# sw-4416-project-v1.net
KiCad netlist of a schematic drawn in EAGLE
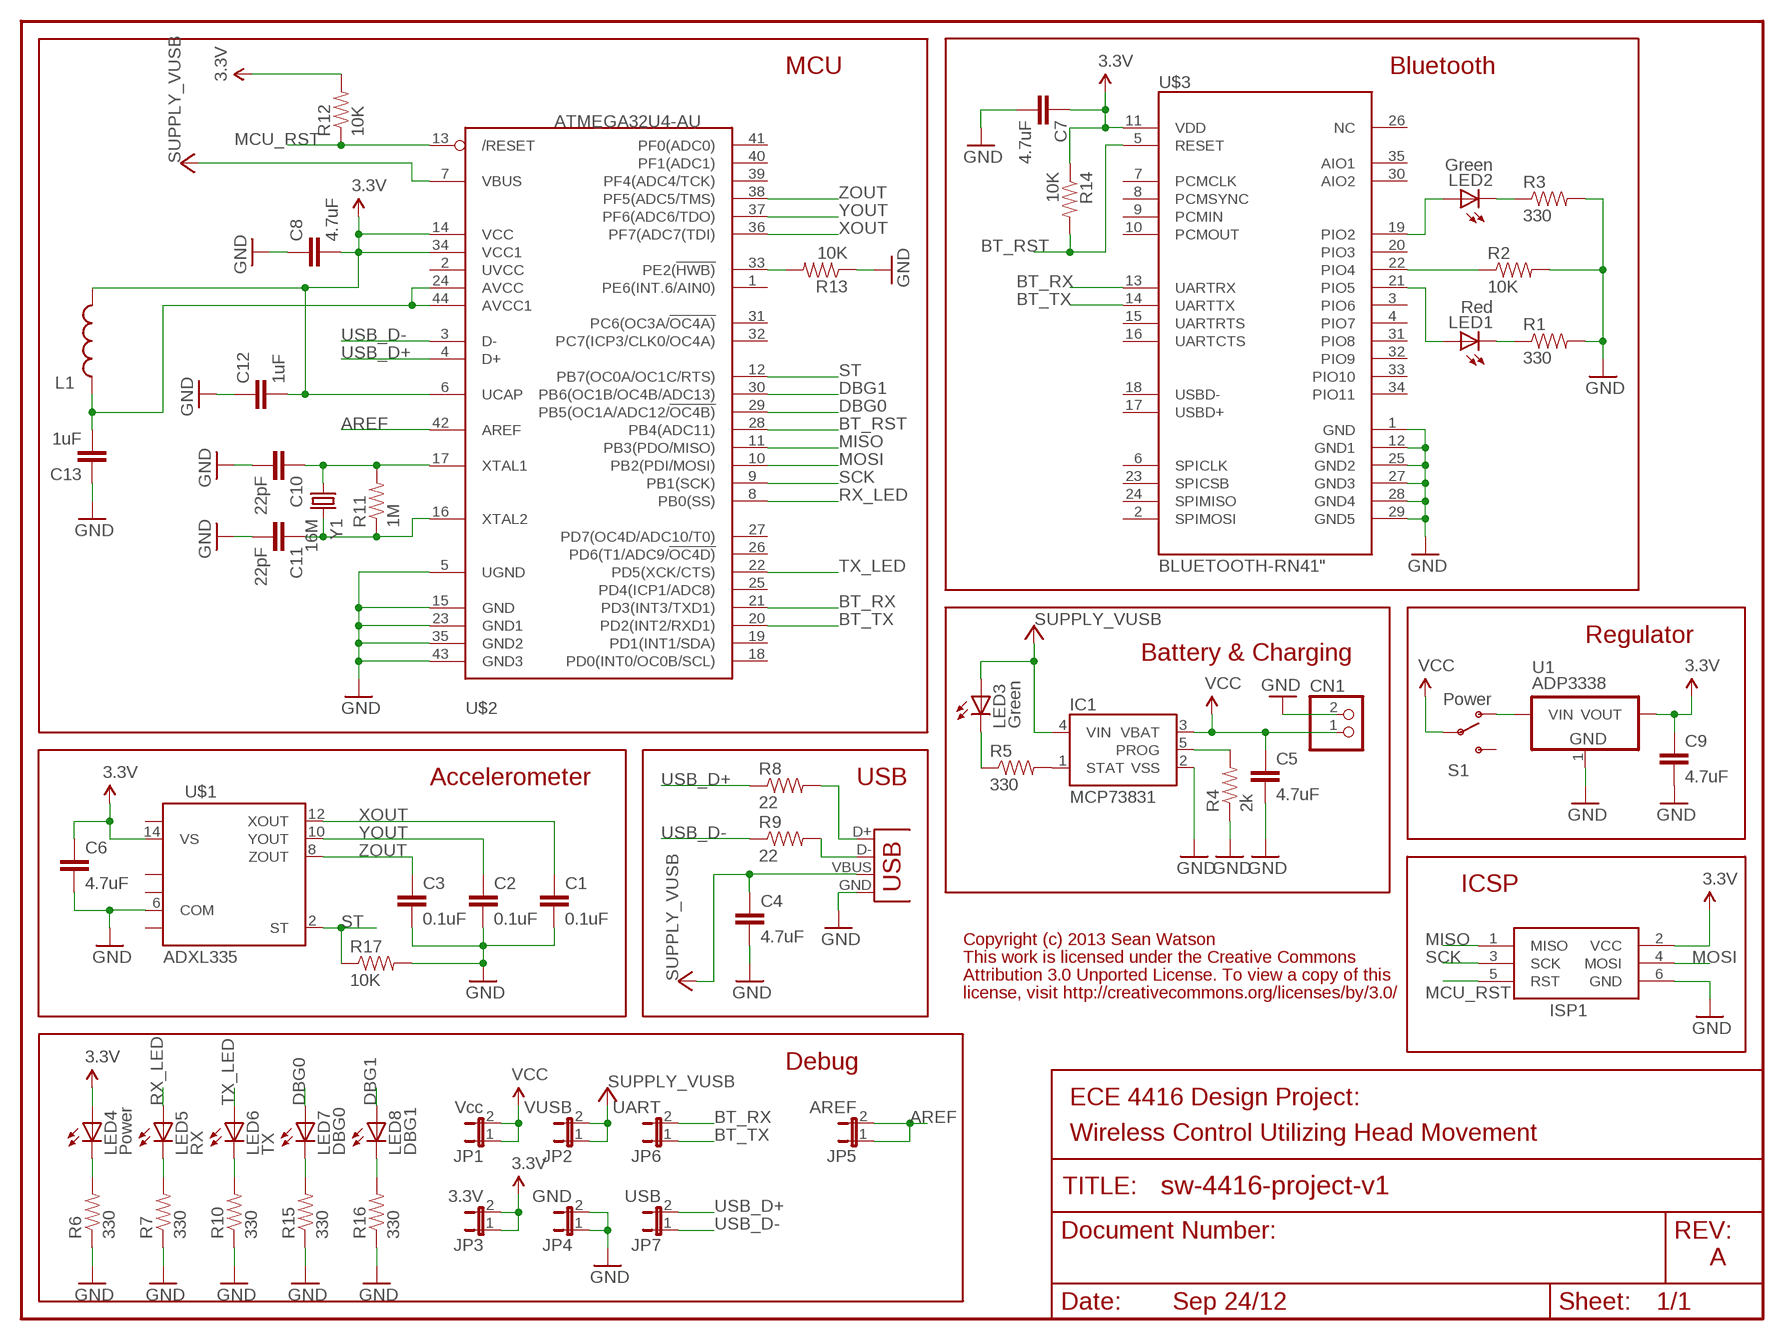
[diagram p0: schematic, sheet 1]

(export (version "E")
  (design (tool "Eeschema 10.0.6"))
  (components
    (comp (ref "C1")
      (value "0.1uF")
      (footprint "eagle-import:0603-CAP")
      (libsource (lib "eagle-import") (part "CAP0603-CAP"))
    )
    (comp (ref "C2")
      (value "0.1uF")
      (footprint "eagle-import:0603-CAP")
      (libsource (lib "eagle-import") (part "CAP0603-CAP"))
    )
    (comp (ref "C3")
      (value "0.1uF")
      (footprint "eagle-import:0603-CAP")
      (libsource (lib "eagle-import") (part "CAP0603-CAP"))
    )
    (comp (ref "C4")
      (value "4.7uF")
      (footprint "eagle-import:0603-CAP")
      (libsource (lib "eagle-import") (part "CAP0603-CAP"))
    )
    (comp (ref "C5")
      (value "4.7uF")
      (footprint "eagle-import:0603-CAP")
      (libsource (lib "eagle-import") (part "CAP0603-CAP"))
    )
    (comp (ref "C6")
      (value "4.7uF")
      (footprint "eagle-import:0603-CAP")
      (libsource (lib "eagle-import") (part "CAP0603-CAP"))
    )
    (comp (ref "C7")
      (value "4.7uF")
      (footprint "eagle-import:0603-CAP")
      (libsource (lib "eagle-import") (part "CAP0603-CAP"))
    )
    (comp (ref "C8")
      (value "4.7uF")
      (footprint "eagle-import:0603-CAP")
      (libsource (lib "eagle-import") (part "CAP0603-CAP"))
    )
    (comp (ref "C9")
      (value "4.7uF")
      (footprint "eagle-import:0603-CAP")
      (libsource (lib "eagle-import") (part "CAP0603-CAP"))
    )
    (comp (ref "C10")
      (value "22pF")
      (footprint "eagle-import:0603-CAP")
      (libsource (lib "eagle-import") (part "CAP0603-CAP"))
    )
    (comp (ref "C11")
      (value "22pF")
      (footprint "eagle-import:0603-CAP")
      (libsource (lib "eagle-import") (part "CAP0603-CAP"))
    )
    (comp (ref "C12")
      (value "1uF")
      (footprint "eagle-import:0603-CAP")
      (libsource (lib "eagle-import") (part "CAP0603-CAP"))
    )
    (comp (ref "C13")
      (value "1uF")
      (footprint "eagle-import:0603-CAP")
      (libsource (lib "eagle-import") (part "CAP0603-CAP"))
    )
    (comp (ref "CN1")
      (value "JST_2PIN-SMT-RA")
      (footprint "eagle-import:JST-PH-2-SMT-RA")
      (libsource (lib "eagle-import") (part "JST_2PIN-SMT-RA"))
    )
    (comp (ref "IC1")
      (value "MCP73831")
      (footprint "eagle-import:SOT23-5")
      (libsource (lib "eagle-import") (part "MCP73831"))
    )
    (comp (ref "ISP1")
      (value "AVRISP-6")
      (footprint "eagle-import:AVRISP")
      (libsource (lib "eagle-import") (part "AVRISP-6"))
    )
    (comp (ref "JP1")
      (value "Vcc")
      (footprint "eagle-import:1X02")
      (libsource (lib "eagle-import") (part "JUMPER-2PTH"))
    )
    (comp (ref "JP2")
      (value "VUSB")
      (footprint "eagle-import:1X02")
      (libsource (lib "eagle-import") (part "JUMPER-2PTH"))
    )
    (comp (ref "JP3")
      (value "3.3V")
      (footprint "eagle-import:1X02")
      (libsource (lib "eagle-import") (part "JUMPER-2PTH"))
    )
    (comp (ref "JP4")
      (value "GND")
      (footprint "eagle-import:1X02")
      (libsource (lib "eagle-import") (part "JUMPER-2PTH"))
    )
    (comp (ref "JP5")
      (value "AREF")
      (footprint "eagle-import:1X02")
      (libsource (lib "eagle-import") (part "JUMPER-2PTH"))
    )
    (comp (ref "JP6")
      (value "UART")
      (footprint "eagle-import:1X02")
      (libsource (lib "eagle-import") (part "JUMPER-2PTH"))
    )
    (comp (ref "JP7")
      (value "USB")
      (footprint "eagle-import:1X02")
      (libsource (lib "eagle-import") (part "JUMPER-2PTH"))
    )
    (comp (ref "L1")
      (value "INDUCTOR0805")
      (footprint "eagle-import:0805")
      (libsource (lib "eagle-import") (part "INDUCTOR0805"))
    )
    (comp (ref "LED1")
      (value "Red")
      (footprint "eagle-import:LED-0603")
      (libsource (lib "eagle-import") (part "LED0603"))
    )
    (comp (ref "LED2")
      (value "Green")
      (footprint "eagle-import:LED-0603")
      (libsource (lib "eagle-import") (part "LED0603"))
    )
    (comp (ref "LED3")
      (value "Green")
      (footprint "eagle-import:LED-0603")
      (libsource (lib "eagle-import") (part "LED0603"))
    )
    (comp (ref "LED4")
      (value "Power")
      (footprint "eagle-import:LED-0603")
      (libsource (lib "eagle-import") (part "LED0603"))
    )
    (comp (ref "LED5")
      (value "RX")
      (footprint "eagle-import:LED-0603")
      (libsource (lib "eagle-import") (part "LED0603"))
    )
    (comp (ref "LED6")
      (value "TX")
      (footprint "eagle-import:LED-0603")
      (libsource (lib "eagle-import") (part "LED0603"))
    )
    (comp (ref "LED7")
      (value "DBG0")
      (footprint "eagle-import:LED-0603")
      (libsource (lib "eagle-import") (part "LED0603"))
    )
    (comp (ref "LED8")
      (value "DBG1")
      (footprint "eagle-import:LED-0603")
      (libsource (lib "eagle-import") (part "LED0603"))
    )
    (comp (ref "R1")
      (value "330")
      (footprint "eagle-import:0603-RES")
      (libsource (lib "eagle-import") (part "RESISTOR0603-RES"))
    )
    (comp (ref "R2")
      (value "10K")
      (footprint "eagle-import:0603-RES")
      (libsource (lib "eagle-import") (part "RESISTOR0603-RES"))
    )
    (comp (ref "R3")
      (value "330")
      (footprint "eagle-import:0603-RES")
      (libsource (lib "eagle-import") (part "RESISTOR0603-RES"))
    )
    (comp (ref "R4")
      (value "2k")
      (footprint "eagle-import:0603-RES")
      (libsource (lib "eagle-import") (part "RESISTOR0603-RES"))
    )
    (comp (ref "R5")
      (value "330")
      (footprint "eagle-import:0603-RES")
      (libsource (lib "eagle-import") (part "RESISTOR0603-RES"))
    )
    (comp (ref "R6")
      (value "330")
      (footprint "eagle-import:0603-RES")
      (libsource (lib "eagle-import") (part "RESISTOR0603-RES"))
    )
    (comp (ref "R7")
      (value "330")
      (footprint "eagle-import:0603-RES")
      (libsource (lib "eagle-import") (part "RESISTOR0603-RES"))
    )
    (comp (ref "R8")
      (value "22")
      (footprint "eagle-import:0603-RES")
      (libsource (lib "eagle-import") (part "RESISTOR0603-RES"))
    )
    (comp (ref "R9")
      (value "22")
      (footprint "eagle-import:0603-RES")
      (libsource (lib "eagle-import") (part "RESISTOR0603-RES"))
    )
    (comp (ref "R10")
      (value "330")
      (footprint "eagle-import:0603-RES")
      (libsource (lib "eagle-import") (part "RESISTOR0603-RES"))
    )
    (comp (ref "R11")
      (value "1M")
      (footprint "eagle-import:0603-RES")
      (libsource (lib "eagle-import") (part "RESISTOR0603-RES"))
    )
    (comp (ref "R12")
      (value "10K")
      (footprint "eagle-import:0603-RES")
      (libsource (lib "eagle-import") (part "RESISTOR0603-RES"))
    )
    (comp (ref "R13")
      (value "10K")
      (footprint "eagle-import:0603-RES")
      (libsource (lib "eagle-import") (part "RESISTOR0603-RES"))
    )
    (comp (ref "R14")
      (value "10K")
      (footprint "eagle-import:0603-RES")
      (libsource (lib "eagle-import") (part "RESISTOR0603-RES"))
    )
    (comp (ref "R15")
      (value "330")
      (footprint "eagle-import:0603-RES")
      (libsource (lib "eagle-import") (part "RESISTOR0603-RES"))
    )
    (comp (ref "R16")
      (value "330")
      (footprint "eagle-import:0603-RES")
      (libsource (lib "eagle-import") (part "RESISTOR0603-RES"))
    )
    (comp (ref "R17")
      (value "10K")
      (footprint "eagle-import:0603-RES")
      (libsource (lib "eagle-import") (part "RESISTOR0603-RES"))
    )
    (comp (ref "S1")
      (value "Power")
      (footprint "eagle-import:SWITCH-SPST-SMD-A")
      (libsource (lib "eagle-import") (part "SWITCH-SPST-SMD-A"))
    )
    (comp (ref "U$1")
      (value "ADXL335")
      (footprint "eagle-import:LFCSP-16")
      (libsource (lib "eagle-import") (part "ADXL335"))
    )
    (comp (ref "U$2")
      (value "ATMEGA32U4-AU")
      (footprint "eagle-import:TQFP44")
      (libsource (lib "eagle-import") (part "ATMEGA32U4-AU"))
    )
    (comp (ref "U$3")
      (value "BLUETOOTH-RN41\"")
      (footprint "eagle-import:RN41")
      (libsource (lib "eagle-import") (part "BLUETOOTH-RN41{dblquote}"))
    )
    (comp (ref "U1")
      (value "ADP3338")
      (footprint "eagle-import:SOT-223")
      (libsource (lib "eagle-import") (part "VREG_3PINS-SOT-223"))
    )
    (comp (ref "X1")
      (value "USB-MICROB")
      (footprint "eagle-import:USB-MICROB")
      (libsource (lib "eagle-import") (part "USB-MICROB"))
    )
    (comp (ref "Y1")
      (value "16M")
      (footprint "eagle-import:HC49US")
      (libsource (lib "eagle-import") (part "CRYSTALHC49US"))
    )
  )
  (nets
    (net (code "1") (name "/AREF") (class "Default")
      (node (ref "JP5") (pin "1") (pinfunction "1_1") (pintype "passive"))
      (node (ref "JP5") (pin "2") (pinfunction "2_2") (pintype "passive"))
      (node (ref "U$2") (pin "42") (pinfunction "AREF_42") (pintype "bidirectional"))
    )
    (net (code "2") (name "/BT_RST") (class "Default")
      (node (ref "R14") (pin "2") (pinfunction "2_2") (pintype "passive"))
      (node (ref "U$2") (pin "28") (pinfunction "PB4(ADC11)_28") (pintype "bidirectional"))
      (node (ref "U$3") (pin "5") (pinfunction "RESET_5") (pintype "bidirectional"))
    )
    (net (code "3") (name "/BT_RX") (class "Default")
      (node (ref "JP6") (pin "2") (pinfunction "2_2") (pintype "passive"))
      (node (ref "U$2") (pin "21") (pinfunction "PD3(INT3/TXD1)_21") (pintype "bidirectional"))
      (node (ref "U$3") (pin "13") (pinfunction "UARTRX_13") (pintype "bidirectional"))
    )
    (net (code "4") (name "/BT_TX") (class "Default")
      (node (ref "JP6") (pin "1") (pinfunction "1_1") (pintype "passive"))
      (node (ref "U$2") (pin "20") (pinfunction "PD2(INT2/RXD1)_20") (pintype "bidirectional"))
      (node (ref "U$3") (pin "14") (pinfunction "UARTTX_14") (pintype "bidirectional"))
    )
    (net (code "5") (name "/DBG0") (class "Default")
      (node (ref "LED7") (pin "A") (pinfunction "A_A") (pintype "passive"))
      (node (ref "U$2") (pin "29") (pinfunction "PB5(OC1A/ADC12/~{OC4B})_29") (pintype "bidirectional"))
    )
    (net (code "6") (name "/DBG1") (class "Default")
      (node (ref "LED8") (pin "A") (pinfunction "A_A") (pintype "passive"))
      (node (ref "U$2") (pin "30") (pinfunction "PB6(OC1B/OC4B/ADC13)_30") (pintype "bidirectional"))
    )
    (net (code "7") (name "/MCU_RST") (class "Default")
      (node (ref "ISP1") (pin "5") (pinfunction "RST_5") (pintype "output"))
      (node (ref "R12") (pin "1") (pinfunction "1_1") (pintype "passive"))
      (node (ref "U$2") (pin "13") (pinfunction "/RESET_13") (pintype "bidirectional"))
    )
    (net (code "8") (name "/MISO") (class "Default")
      (node (ref "ISP1") (pin "1") (pinfunction "MISO_1") (pintype "input"))
      (node (ref "U$2") (pin "11") (pinfunction "PB3(PDO/MISO)_11") (pintype "bidirectional"))
    )
    (net (code "9") (name "/MOSI") (class "Default")
      (node (ref "ISP1") (pin "4") (pinfunction "MOSI_4") (pintype "output"))
      (node (ref "U$2") (pin "10") (pinfunction "PB2(PDI/MOSI)_10") (pintype "bidirectional"))
    )
    (net (code "10") (name "/RX_LED") (class "Default")
      (node (ref "LED5") (pin "A") (pinfunction "A_A") (pintype "passive"))
      (node (ref "U$2") (pin "8") (pinfunction "PB0(SS)_8") (pintype "bidirectional"))
    )
    (net (code "11") (name "/SCK") (class "Default")
      (node (ref "ISP1") (pin "3") (pinfunction "SCK_3") (pintype "output"))
      (node (ref "U$2") (pin "9") (pinfunction "PB1(SCK)_9") (pintype "bidirectional"))
    )
    (net (code "12") (name "/ST") (class "Default")
      (node (ref "R17") (pin "1") (pinfunction "1_1") (pintype "passive"))
      (node (ref "U$1") (pin "2") (pinfunction "ST_2") (pintype "bidirectional"))
      (node (ref "U$2") (pin "12") (pinfunction "PB7(OC0A/OC1C/RTS)_12") (pintype "bidirectional"))
    )
    (net (code "13") (name "/TX_LED") (class "Default")
      (node (ref "LED6") (pin "A") (pinfunction "A_A") (pintype "passive"))
      (node (ref "U$2") (pin "22") (pinfunction "PD5(XCK/CTS)_22") (pintype "bidirectional"))
    )
    (net (code "14") (name "/USB_D+") (class "Default")
      (node (ref "JP7") (pin "2") (pinfunction "2_2") (pintype "passive"))
      (node (ref "R8") (pin "1") (pinfunction "1_1") (pintype "passive"))
      (node (ref "U$2") (pin "4") (pinfunction "D+_4") (pintype "bidirectional"))
    )
    (net (code "15") (name "/USB_D-") (class "Default")
      (node (ref "JP7") (pin "1") (pinfunction "1_1") (pintype "passive"))
      (node (ref "R9") (pin "1") (pinfunction "1_1") (pintype "passive"))
      (node (ref "U$2") (pin "3") (pinfunction "D-_3") (pintype "bidirectional"))
    )
    (net (code "16") (name "/XOUT") (class "Default")
      (node (ref "C1") (pin "1") (pinfunction "1_1") (pintype "passive"))
      (node (ref "U$1") (pin "12") (pinfunction "XOUT_12") (pintype "bidirectional"))
      (node (ref "U$2") (pin "36") (pinfunction "PF7(ADC7(TDI)_36") (pintype "bidirectional"))
    )
    (net (code "17") (name "/YOUT") (class "Default")
      (node (ref "C2") (pin "1") (pinfunction "1_1") (pintype "passive"))
      (node (ref "U$1") (pin "10") (pinfunction "YOUT_10") (pintype "bidirectional"))
      (node (ref "U$2") (pin "37") (pinfunction "PF6(ADC6/TDO)_37") (pintype "bidirectional"))
    )
    (net (code "18") (name "/ZOUT") (class "Default")
      (node (ref "C3") (pin "1") (pinfunction "1_1") (pintype "passive"))
      (node (ref "U$1") (pin "8") (pinfunction "ZOUT_8") (pintype "bidirectional"))
      (node (ref "U$2") (pin "38") (pinfunction "PF5(ADC5/TMS)_38") (pintype "bidirectional"))
    )
    (net (code "19") (name "3.3V") (class "Default")
      (node (ref "C12") (pin "2") (pinfunction "2_2") (pintype "passive"))
      (node (ref "C6") (pin "1") (pinfunction "1_1") (pintype "passive"))
      (node (ref "C7") (pin "1") (pinfunction "1_1") (pintype "passive"))
      (node (ref "C8") (pin "2") (pinfunction "2_2") (pintype "passive"))
      (node (ref "C9") (pin "1") (pinfunction "1_1") (pintype "passive"))
      (node (ref "ISP1") (pin "2") (pinfunction "VCC_2") (pintype "power_in"))
      (node (ref "JP3") (pin "1") (pinfunction "1_1") (pintype "passive"))
      (node (ref "JP3") (pin "2") (pinfunction "2_2") (pintype "passive"))
      (node (ref "L1") (pin "2") (pinfunction "2_2") (pintype "passive"))
      (node (ref "LED4") (pin "A") (pinfunction "A_A") (pintype "passive"))
      (node (ref "R12") (pin "2") (pinfunction "2_2") (pintype "passive"))
      (node (ref "R14") (pin "1") (pinfunction "1_1") (pintype "passive"))
      (node (ref "U$1") (pin "14") (pinfunction "VS_14") (pintype "bidirectional"))
      (node (ref "U$2") (pin "14") (pinfunction "VCC_14") (pintype "bidirectional"))
      (node (ref "U$2") (pin "34") (pinfunction "VCC1_34") (pintype "bidirectional"))
      (node (ref "U$2") (pin "6") (pinfunction "UCAP_6") (pintype "bidirectional"))
      (node (ref "U$3") (pin "11") (pinfunction "VDD_11") (pintype "bidirectional"))
      (node (ref "U1") (pin "2") (pinfunction "VOUT_2") (pintype "bidirectional"))
    )
    (net (code "20") (name "GND") (class "Default")
      (node (ref "C1") (pin "2") (pinfunction "2_2") (pintype "passive"))
      (node (ref "C10") (pin "2") (pinfunction "2_2") (pintype "passive"))
      (node (ref "C11") (pin "2") (pinfunction "2_2") (pintype "passive"))
      (node (ref "C12") (pin "1") (pinfunction "1_1") (pintype "passive"))
      (node (ref "C13") (pin "1") (pinfunction "1_1") (pintype "passive"))
      (node (ref "C2") (pin "2") (pinfunction "2_2") (pintype "passive"))
      (node (ref "C3") (pin "2") (pinfunction "2_2") (pintype "passive"))
      (node (ref "C4") (pin "2") (pinfunction "2_2") (pintype "passive"))
      (node (ref "C5") (pin "2") (pinfunction "2_2") (pintype "passive"))
      (node (ref "C6") (pin "2") (pinfunction "2_2") (pintype "passive"))
      (node (ref "C7") (pin "2") (pinfunction "2_2") (pintype "passive"))
      (node (ref "C8") (pin "1") (pinfunction "1_1") (pintype "passive"))
      (node (ref "C9") (pin "2") (pinfunction "2_2") (pintype "passive"))
      (node (ref "CN1") (pin "2") (pinfunction "1_2") (pintype "passive"))
      (node (ref "IC1") (pin "2") (pinfunction "VSS_2") (pintype "power_in"))
      (node (ref "ISP1") (pin "6") (pinfunction "GND_6") (pintype "power_in"))
      (node (ref "JP4") (pin "1") (pinfunction "1_1") (pintype "passive"))
      (node (ref "JP4") (pin "2") (pinfunction "2_2") (pintype "passive"))
      (node (ref "R1") (pin "2") (pinfunction "2_2") (pintype "passive"))
      (node (ref "R10") (pin "1") (pinfunction "1_1") (pintype "passive"))
      (node (ref "R13") (pin "1") (pinfunction "1_1") (pintype "passive"))
      (node (ref "R15") (pin "1") (pinfunction "1_1") (pintype "passive"))
      (node (ref "R16") (pin "1") (pinfunction "1_1") (pintype "passive"))
      (node (ref "R17") (pin "2") (pinfunction "2_2") (pintype "passive"))
      (node (ref "R2") (pin "2") (pinfunction "2_2") (pintype "passive"))
      (node (ref "R3") (pin "2") (pinfunction "2_2") (pintype "passive"))
      (node (ref "R4") (pin "1") (pinfunction "1_1") (pintype "passive"))
      (node (ref "R6") (pin "1") (pinfunction "1_1") (pintype "passive"))
      (node (ref "R7") (pin "1") (pinfunction "1_1") (pintype "passive"))
      (node (ref "U$1") (pin "6") (pinfunction "COM_6") (pintype "bidirectional"))
      (node (ref "U$2") (pin "15") (pinfunction "GND_15") (pintype "bidirectional"))
      (node (ref "U$2") (pin "23") (pinfunction "GND1_23") (pintype "bidirectional"))
      (node (ref "U$2") (pin "35") (pinfunction "GND2_35") (pintype "bidirectional"))
      (node (ref "U$2") (pin "43") (pinfunction "GND3_43") (pintype "bidirectional"))
      (node (ref "U$2") (pin "5") (pinfunction "UGND_5") (pintype "bidirectional"))
      (node (ref "U$3") (pin "1") (pinfunction "GND_1") (pintype "bidirectional"))
      (node (ref "U$3") (pin "12") (pinfunction "GND1_12") (pintype "bidirectional"))
      (node (ref "U$3") (pin "25") (pinfunction "GND2_25") (pintype "bidirectional"))
      (node (ref "U$3") (pin "27") (pinfunction "GND3_27") (pintype "bidirectional"))
      (node (ref "U$3") (pin "28") (pinfunction "GND4_28") (pintype "bidirectional"))
      (node (ref "U$3") (pin "29") (pinfunction "GND5_29") (pintype "bidirectional"))
      (node (ref "U1") (pin "1") (pinfunction "GND_1") (pintype "bidirectional"))
      (node (ref "X1") (pin "GND") (pinfunction "GND_GND") (pintype "bidirectional"))
    )
    (net (code "21") (name "Net-(IC1-PROG)") (class "Default")
      (node (ref "IC1") (pin "5") (pinfunction "PROG_5") (pintype "input"))
      (node (ref "R4") (pin "2") (pinfunction "2_2") (pintype "passive"))
    )
    (net (code "22") (name "Net-(IC1-STAT)") (class "Default")
      (node (ref "IC1") (pin "1") (pinfunction "STAT_1") (pintype "output"))
      (node (ref "R5") (pin "2") (pinfunction "2_2") (pintype "passive"))
    )
    (net (code "23") (name "Net-(LED1-PadC)") (class "Default")
      (node (ref "LED1") (pin "C") (pinfunction "C_C") (pintype "passive"))
      (node (ref "R1") (pin "1") (pinfunction "1_1") (pintype "passive"))
    )
    (net (code "24") (name "Net-(LED2-PadC)") (class "Default")
      (node (ref "LED2") (pin "C") (pinfunction "C_C") (pintype "passive"))
      (node (ref "R3") (pin "1") (pinfunction "1_1") (pintype "passive"))
    )
    (net (code "25") (name "Net-(LED3-PadC)") (class "Default")
      (node (ref "LED3") (pin "C") (pinfunction "C_C") (pintype "passive"))
      (node (ref "R5") (pin "1") (pinfunction "1_1") (pintype "passive"))
    )
    (net (code "26") (name "Net-(LED4-PadC)") (class "Default")
      (node (ref "LED4") (pin "C") (pinfunction "C_C") (pintype "passive"))
      (node (ref "R6") (pin "2") (pinfunction "2_2") (pintype "passive"))
    )
    (net (code "27") (name "Net-(LED5-PadC)") (class "Default")
      (node (ref "LED5") (pin "C") (pinfunction "C_C") (pintype "passive"))
      (node (ref "R7") (pin "2") (pinfunction "2_2") (pintype "passive"))
    )
    (net (code "28") (name "Net-(LED6-PadC)") (class "Default")
      (node (ref "LED6") (pin "C") (pinfunction "C_C") (pintype "passive"))
      (node (ref "R10") (pin "2") (pinfunction "2_2") (pintype "passive"))
    )
    (net (code "29") (name "Net-(LED7-PadC)") (class "Default")
      (node (ref "LED7") (pin "C") (pinfunction "C_C") (pintype "passive"))
      (node (ref "R15") (pin "2") (pinfunction "2_2") (pintype "passive"))
    )
    (net (code "30") (name "Net-(LED8-PadC)") (class "Default")
      (node (ref "LED8") (pin "C") (pinfunction "C_C") (pintype "passive"))
      (node (ref "R16") (pin "2") (pinfunction "2_2") (pintype "passive"))
    )
    (net (code "31") (name "Net-(R8-Pad2)") (class "Default")
      (node (ref "R8") (pin "2") (pinfunction "2_2") (pintype "passive"))
      (node (ref "X1") (pin "D+") (pinfunction "D+_D+") (pintype "bidirectional"))
    )
    (net (code "32") (name "Net-(R9-Pad2)") (class "Default")
      (node (ref "R9") (pin "2") (pinfunction "2_2") (pintype "passive"))
      (node (ref "X1") (pin "D-") (pinfunction "D-_D-") (pintype "bidirectional"))
    )
    (net (code "33") (name "Net-(S1-O)") (class "Default")
      (node (ref "S1") (pin "1") (pinfunction "O_1") (pintype "passive"))
      (node (ref "U1") (pin "3") (pinfunction "VIN_3") (pintype "bidirectional"))
    )
    (net (code "34") (name "Net-(U$2-AVCC)") (class "Default")
      (node (ref "C13") (pin "2") (pinfunction "2_2") (pintype "passive"))
      (node (ref "L1") (pin "1") (pinfunction "1_1") (pintype "passive"))
      (node (ref "U$2") (pin "24") (pinfunction "AVCC_24") (pintype "bidirectional"))
      (node (ref "U$2") (pin "44") (pinfunction "AVCC1_44") (pintype "bidirectional"))
    )
    (net (code "35") (name "Net-(U$2-PE2(~{HWB}))") (class "Default")
      (node (ref "R13") (pin "2") (pinfunction "2_2") (pintype "passive"))
      (node (ref "U$2") (pin "33") (pinfunction "PE2(~{HWB})_33") (pintype "bidirectional"))
    )
    (net (code "36") (name "Net-(U$2-XTAL1)") (class "Default")
      (node (ref "C10") (pin "1") (pinfunction "1_1") (pintype "passive"))
      (node (ref "R11") (pin "2") (pinfunction "2_2") (pintype "passive"))
      (node (ref "U$2") (pin "17") (pinfunction "XTAL1_17") (pintype "bidirectional"))
      (node (ref "Y1") (pin "1") (pinfunction "1_1") (pintype "passive"))
    )
    (net (code "37") (name "Net-(U$2-XTAL2)") (class "Default")
      (node (ref "C11") (pin "1") (pinfunction "1_1") (pintype "passive"))
      (node (ref "R11") (pin "1") (pinfunction "1_1") (pintype "passive"))
      (node (ref "U$2") (pin "16") (pinfunction "XTAL2_16") (pintype "bidirectional"))
      (node (ref "Y1") (pin "2") (pinfunction "2_2") (pintype "passive"))
    )
    (net (code "38") (name "Net-(U$3-PIO2)") (class "Default")
      (node (ref "LED2") (pin "A") (pinfunction "A_A") (pintype "passive"))
      (node (ref "U$3") (pin "19") (pinfunction "PIO2_19") (pintype "bidirectional"))
    )
    (net (code "39") (name "Net-(U$3-PIO4)") (class "Default")
      (node (ref "R2") (pin "1") (pinfunction "1_1") (pintype "passive"))
      (node (ref "U$3") (pin "22") (pinfunction "PIO4_22") (pintype "bidirectional"))
    )
    (net (code "40") (name "Net-(U$3-PIO5)") (class "Default")
      (node (ref "LED1") (pin "A") (pinfunction "A_A") (pintype "passive"))
      (node (ref "U$3") (pin "21") (pinfunction "PIO5_21") (pintype "bidirectional"))
    )
    (net (code "41") (name "SUPPLY_VUSB") (class "Default")
      (node (ref "C4") (pin "1") (pinfunction "1_1") (pintype "passive"))
      (node (ref "IC1") (pin "4") (pinfunction "VIN_4") (pintype "power_in"))
      (node (ref "JP2") (pin "1") (pinfunction "1_1") (pintype "passive"))
      (node (ref "JP2") (pin "2") (pinfunction "2_2") (pintype "passive"))
      (node (ref "LED3") (pin "A") (pinfunction "A_A") (pintype "passive"))
      (node (ref "U$2") (pin "7") (pinfunction "VBUS_7") (pintype "bidirectional"))
      (node (ref "X1") (pin "VBUS") (pinfunction "VBUS_VBUS") (pintype "bidirectional"))
    )
    (net (code "42") (name "VCC") (class "Default")
      (node (ref "C5") (pin "1") (pinfunction "1_1") (pintype "passive"))
      (node (ref "CN1") (pin "1") (pinfunction "2_1") (pintype "passive"))
      (node (ref "IC1") (pin "3") (pinfunction "VBAT_3") (pintype "power_in"))
      (node (ref "JP1") (pin "1") (pinfunction "1_1") (pintype "passive"))
      (node (ref "JP1") (pin "2") (pinfunction "2_2") (pintype "passive"))
      (node (ref "S1") (pin "2") (pinfunction "P_2") (pintype "passive"))
    )
    (net (code "43") (name "unconnected-(S1-S-Pad3)") (class "Default")
      (node (ref "S1") (pin "3") (pinfunction "S_3") (pintype "passive"))
    )
    (net (code "44") (name "unconnected-(U$1-COM-Pad3)") (class "Default")
      (node (ref "U$1") (pin "3") (pinfunction "COM_3") (pintype "bidirectional"))
    )
    (net (code "45") (name "unconnected-(U$1-COM-Pad5)") (class "Default")
      (node (ref "U$1") (pin "5") (pinfunction "COM_5") (pintype "bidirectional"))
    )
    (net (code "46") (name "unconnected-(U$1-COM-Pad7)") (class "Default")
      (node (ref "U$1") (pin "7") (pinfunction "COM_7") (pintype "bidirectional"))
    )
    (net (code "47") (name "unconnected-(U$1-VS-Pad15)") (class "Default")
      (node (ref "U$1") (pin "15") (pinfunction "VS_15") (pintype "bidirectional"))
    )
    (net (code "48") (name "unconnected-(U$2-PC6(OC3A{slash}~{OC4A})-Pad31)") (class "Default")
      (node (ref "U$2") (pin "31") (pinfunction "PC6(OC3A/~{OC4A})_31") (pintype "bidirectional"))
    )
    (net (code "49") (name "unconnected-(U$2-PC7(ICP3{slash}CLK0{slash}OC4A)-Pad32)") (class "Default")
      (node (ref "U$2") (pin "32") (pinfunction "PC7(ICP3/CLK0/OC4A)_32") (pintype "bidirectional"))
    )
    (net (code "50") (name "unconnected-(U$2-PD0(INT0{slash}OC0B{slash}SCL)-Pad18)") (class "Default")
      (node (ref "U$2") (pin "18") (pinfunction "PD0(INT0/OC0B/SCL)_18") (pintype "bidirectional"))
    )
    (net (code "51") (name "unconnected-(U$2-PD1(INT1{slash}SDA)-Pad19)") (class "Default")
      (node (ref "U$2") (pin "19") (pinfunction "PD1(INT1/SDA)_19") (pintype "bidirectional"))
    )
    (net (code "52") (name "unconnected-(U$2-PD4(ICP1{slash}ADC8)-Pad25)") (class "Default")
      (node (ref "U$2") (pin "25") (pinfunction "PD4(ICP1/ADC8)_25") (pintype "bidirectional"))
    )
    (net (code "53") (name "unconnected-(U$2-PD6(T1{slash}ADC9{slash}~{OC4D})-Pad26)") (class "Default")
      (node (ref "U$2") (pin "26") (pinfunction "PD6(T1/ADC9/~{OC4D})_26") (pintype "bidirectional"))
    )
    (net (code "54") (name "unconnected-(U$2-PD7(OC4D{slash}ADC10{slash}T0)-Pad27)") (class "Default")
      (node (ref "U$2") (pin "27") (pinfunction "PD7(OC4D/ADC10/T0)_27") (pintype "bidirectional"))
    )
    (net (code "55") (name "unconnected-(U$2-PE6(INT.6{slash}AIN0)-Pad1)") (class "Default")
      (node (ref "U$2") (pin "1") (pinfunction "PE6(INT.6/AIN0)_1") (pintype "bidirectional"))
    )
    (net (code "56") (name "unconnected-(U$2-PF0(ADC0)-Pad41)") (class "Default")
      (node (ref "U$2") (pin "41") (pinfunction "PF0(ADC0)_41") (pintype "bidirectional"))
    )
    (net (code "57") (name "unconnected-(U$2-PF1(ADC1)-Pad40)") (class "Default")
      (node (ref "U$2") (pin "40") (pinfunction "PF1(ADC1)_40") (pintype "bidirectional"))
    )
    (net (code "58") (name "unconnected-(U$2-PF4(ADC4{slash}TCK)-Pad39)") (class "Default")
      (node (ref "U$2") (pin "39") (pinfunction "PF4(ADC4/TCK)_39") (pintype "bidirectional"))
    )
    (net (code "59") (name "unconnected-(U$2-UVCC-Pad2)") (class "Default")
      (node (ref "U$2") (pin "2") (pinfunction "UVCC_2") (pintype "bidirectional"))
    )
    (net (code "60") (name "unconnected-(U$3-AIO1-Pad35)") (class "Default")
      (node (ref "U$3") (pin "35") (pinfunction "AIO1_35") (pintype "bidirectional"))
    )
    (net (code "61") (name "unconnected-(U$3-AIO2-Pad30)") (class "Default")
      (node (ref "U$3") (pin "30") (pinfunction "AIO2_30") (pintype "bidirectional"))
    )
    (net (code "62") (name "unconnected-(U$3-NC-Pad26)") (class "Default")
      (node (ref "U$3") (pin "26") (pinfunction "NC_26") (pintype "bidirectional"))
    )
    (net (code "63") (name "unconnected-(U$3-PCMCLK-Pad7)") (class "Default")
      (node (ref "U$3") (pin "7") (pinfunction "PCMCLK_7") (pintype "bidirectional"))
    )
    (net (code "64") (name "unconnected-(U$3-PCMIN-Pad9)") (class "Default")
      (node (ref "U$3") (pin "9") (pinfunction "PCMIN_9") (pintype "bidirectional"))
    )
    (net (code "65") (name "unconnected-(U$3-PCMOUT-Pad10)") (class "Default")
      (node (ref "U$3") (pin "10") (pinfunction "PCMOUT_10") (pintype "bidirectional"))
    )
    (net (code "66") (name "unconnected-(U$3-PCMSYNC-Pad8)") (class "Default")
      (node (ref "U$3") (pin "8") (pinfunction "PCMSYNC_8") (pintype "bidirectional"))
    )
    (net (code "67") (name "unconnected-(U$3-PIO3-Pad20)") (class "Default")
      (node (ref "U$3") (pin "20") (pinfunction "PIO3_20") (pintype "bidirectional"))
    )
    (net (code "68") (name "unconnected-(U$3-PIO6-Pad3)") (class "Default")
      (node (ref "U$3") (pin "3") (pinfunction "PIO6_3") (pintype "bidirectional"))
    )
    (net (code "69") (name "unconnected-(U$3-PIO7-Pad4)") (class "Default")
      (node (ref "U$3") (pin "4") (pinfunction "PIO7_4") (pintype "bidirectional"))
    )
    (net (code "70") (name "unconnected-(U$3-PIO8-Pad31)") (class "Default")
      (node (ref "U$3") (pin "31") (pinfunction "PIO8_31") (pintype "bidirectional"))
    )
    (net (code "71") (name "unconnected-(U$3-PIO9-Pad32)") (class "Default")
      (node (ref "U$3") (pin "32") (pinfunction "PIO9_32") (pintype "bidirectional"))
    )
    (net (code "72") (name "unconnected-(U$3-PIO10-Pad33)") (class "Default")
      (node (ref "U$3") (pin "33") (pinfunction "PIO10_33") (pintype "bidirectional"))
    )
    (net (code "73") (name "unconnected-(U$3-PIO11-Pad34)") (class "Default")
      (node (ref "U$3") (pin "34") (pinfunction "PIO11_34") (pintype "bidirectional"))
    )
    (net (code "74") (name "unconnected-(U$3-SPICLK-Pad6)") (class "Default")
      (node (ref "U$3") (pin "6") (pinfunction "SPICLK_6") (pintype "bidirectional"))
    )
    (net (code "75") (name "unconnected-(U$3-SPICSB-Pad23)") (class "Default")
      (node (ref "U$3") (pin "23") (pinfunction "SPICSB_23") (pintype "bidirectional"))
    )
    (net (code "76") (name "unconnected-(U$3-SPIMISO-Pad24)") (class "Default")
      (node (ref "U$3") (pin "24") (pinfunction "SPIMISO_24") (pintype "bidirectional"))
    )
    (net (code "77") (name "unconnected-(U$3-SPIMOSI-Pad2)") (class "Default")
      (node (ref "U$3") (pin "2") (pinfunction "SPIMOSI_2") (pintype "bidirectional"))
    )
    (net (code "78") (name "unconnected-(U$3-UARTCTS-Pad16)") (class "Default")
      (node (ref "U$3") (pin "16") (pinfunction "UARTCTS_16") (pintype "bidirectional"))
    )
    (net (code "79") (name "unconnected-(U$3-UARTRTS-Pad15)") (class "Default")
      (node (ref "U$3") (pin "15") (pinfunction "UARTRTS_15") (pintype "bidirectional"))
    )
    (net (code "80") (name "unconnected-(U$3-USBD+-Pad17)") (class "Default")
      (node (ref "U$3") (pin "17") (pinfunction "USBD+_17") (pintype "bidirectional"))
    )
    (net (code "81") (name "unconnected-(U$3-USBD--Pad18)") (class "Default")
      (node (ref "U$3") (pin "18") (pinfunction "USBD-_18") (pintype "bidirectional"))
    )
  )
)
